# exlemon.net
KiCad netlist of a schematic drawn in EAGLE
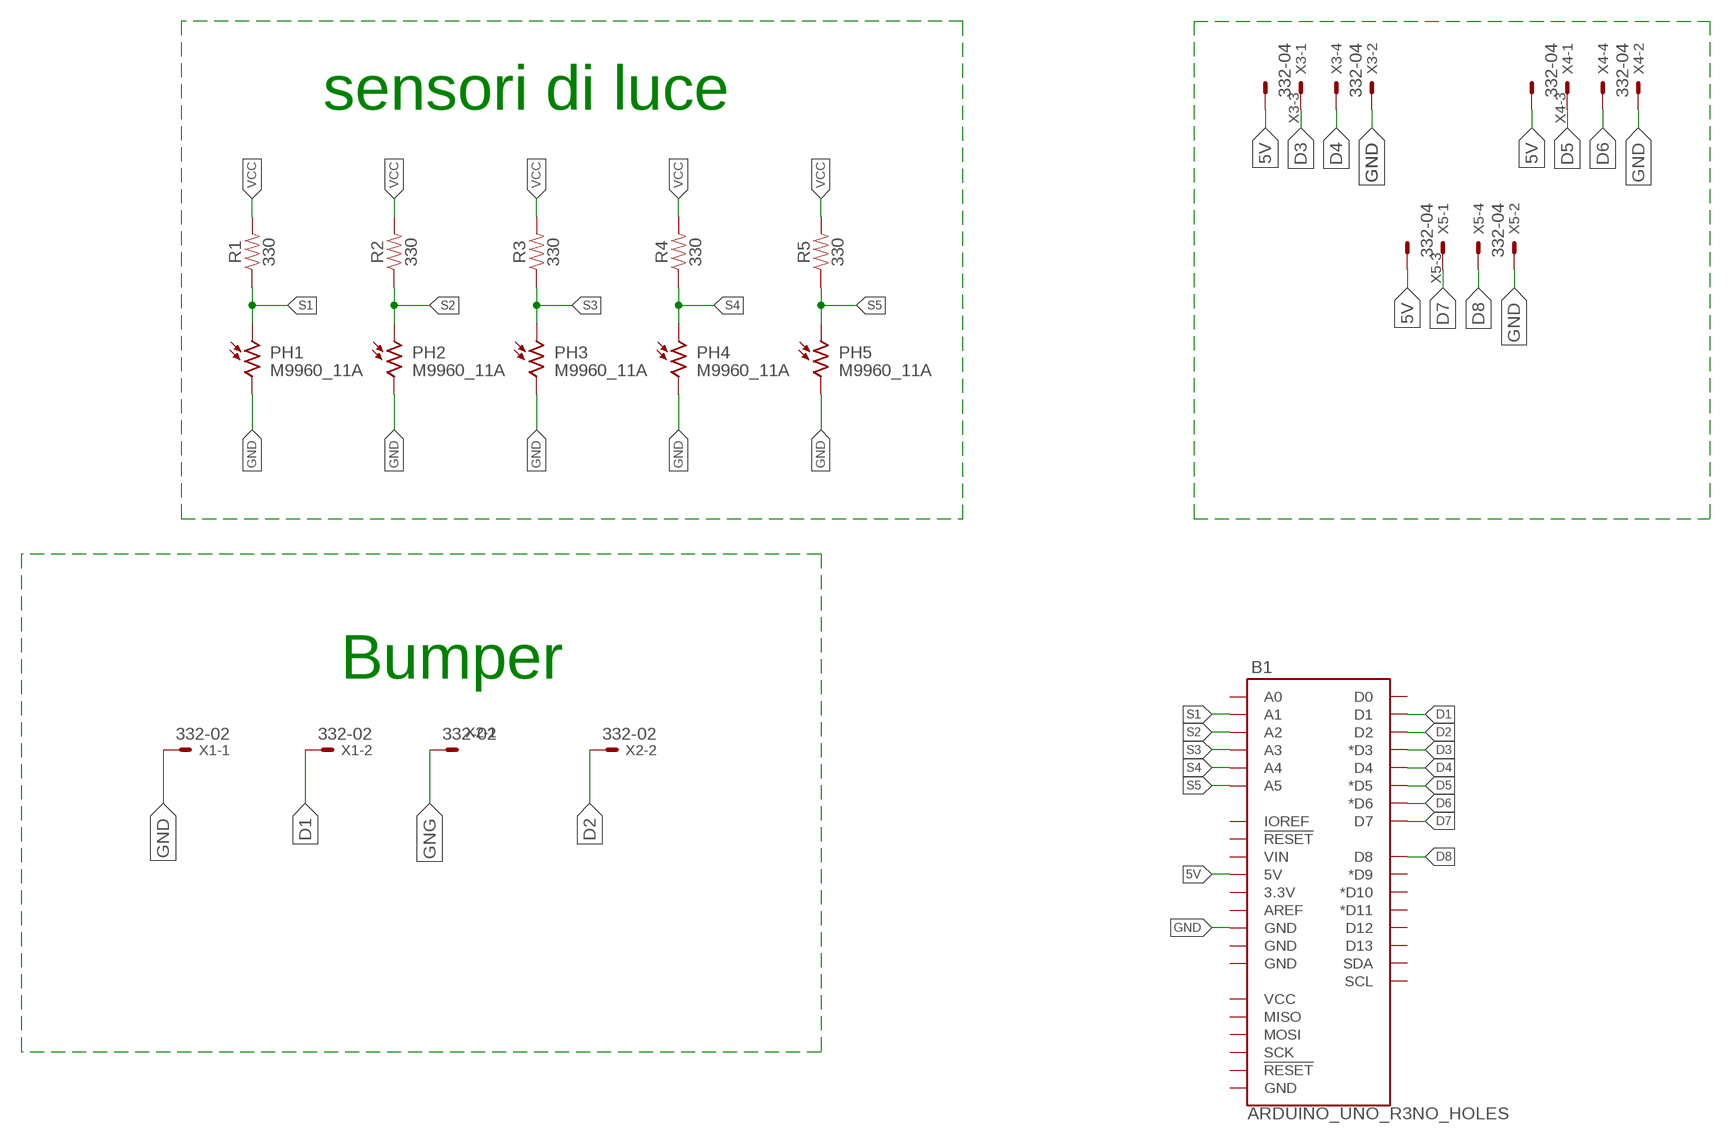
[diagram p0: schematic, sheet 1]

(export (version "E")
  (design (tool "Eeschema 10.0.6"))
  (components
    (comp (ref "B1")
      (value "ARDUINO_UNO_R3NO_HOLES")
      (footprint "eagle-import:ARDUINO_R3_NO_HOLES")
      (libsource (lib "eagle-import") (part "ARDUINO_UNO_R3NO_HOLES"))
    )
    (comp (ref "PH1")
      (value "M9960_11A")
      (footprint "eagle-import:M9960")
      (libsource (lib "eagle-import") (part "M9960_11A"))
    )
    (comp (ref "PH2")
      (value "M9960_11A")
      (footprint "eagle-import:M9960")
      (libsource (lib "eagle-import") (part "M9960_11A"))
    )
    (comp (ref "PH3")
      (value "M9960_11A")
      (footprint "eagle-import:M9960")
      (libsource (lib "eagle-import") (part "M9960_11A"))
    )
    (comp (ref "PH4")
      (value "M9960_11A")
      (footprint "eagle-import:M9960")
      (libsource (lib "eagle-import") (part "M9960_11A"))
    )
    (comp (ref "PH5")
      (value "M9960_11A")
      (footprint "eagle-import:M9960")
      (libsource (lib "eagle-import") (part "M9960_11A"))
    )
    (comp (ref "R1")
      (value "330")
      (footprint "eagle-import:AXIAL-0.3")
      (libsource (lib "eagle-import") (part "330OHM-HORIZ-1/10W-5%"))
    )
    (comp (ref "R2")
      (value "330")
      (footprint "eagle-import:AXIAL-0.3")
      (libsource (lib "eagle-import") (part "330OHM-HORIZ-1/10W-5%"))
    )
    (comp (ref "R3")
      (value "330")
      (footprint "eagle-import:AXIAL-0.3")
      (libsource (lib "eagle-import") (part "330OHM-HORIZ-1/10W-5%"))
    )
    (comp (ref "R4")
      (value "330")
      (footprint "eagle-import:AXIAL-0.3")
      (libsource (lib "eagle-import") (part "330OHM-HORIZ-1/10W-5%"))
    )
    (comp (ref "R5")
      (value "330")
      (footprint "eagle-import:AXIAL-0.3")
      (libsource (lib "eagle-import") (part "330OHM-HORIZ-1/10W-5%"))
    )
    (comp (ref "X1")
      (value "332-02")
      (footprint "eagle-import:332-02")
      (libsource (lib "eagle-import") (part "332-02"))
    )
    (comp (ref "X2")
      (value "332-02")
      (footprint "eagle-import:332-02")
      (libsource (lib "eagle-import") (part "332-02"))
    )
    (comp (ref "X3")
      (value "332-04")
      (footprint "eagle-import:332-04")
      (libsource (lib "eagle-import") (part "332-04"))
    )
    (comp (ref "X4")
      (value "332-04")
      (footprint "eagle-import:332-04")
      (libsource (lib "eagle-import") (part "332-04"))
    )
    (comp (ref "X5")
      (value "332-04")
      (footprint "eagle-import:332-04")
      (libsource (lib "eagle-import") (part "332-04"))
    )
  )
  (nets
    (net (code "2") (name "5V") (class "Default")
      (node (ref "B1") (pin "5V") (pinfunction "5V_5V") (pintype "bidirectional"))
      (node (ref "X3") (pin "3") (pinfunction "S_3") (pintype "passive"))
      (node (ref "X4") (pin "3") (pinfunction "S_3") (pintype "passive"))
      (node (ref "X5") (pin "3") (pinfunction "S_3") (pintype "passive"))
    )
    (net (code "3") (name "D1") (class "Default")
      (node (ref "B1") (pin "D1") (pinfunction "D1_D1") (pintype "bidirectional"))
      (node (ref "X1") (pin "2") (pinfunction "S_2") (pintype "passive"))
    )
    (net (code "4") (name "D2") (class "Default")
      (node (ref "B1") (pin "D2") (pinfunction "D2_D2") (pintype "bidirectional"))
      (node (ref "X2") (pin "2") (pinfunction "S_2") (pintype "passive"))
    )
    (net (code "5") (name "D3") (class "Default")
      (node (ref "B1") (pin "D3") (pinfunction "*D3_D3") (pintype "bidirectional"))
      (node (ref "X3") (pin "1") (pinfunction "S_1") (pintype "passive"))
    )
    (net (code "6") (name "D4") (class "Default")
      (node (ref "B1") (pin "D4") (pinfunction "D4_D4") (pintype "bidirectional"))
      (node (ref "X3") (pin "4") (pinfunction "S_4") (pintype "passive"))
    )
    (net (code "7") (name "D5") (class "Default")
      (node (ref "B1") (pin "D5") (pinfunction "*D5_D5") (pintype "bidirectional"))
      (node (ref "X4") (pin "1") (pinfunction "S_1") (pintype "passive"))
    )
    (net (code "8") (name "D6") (class "Default")
      (node (ref "B1") (pin "D6") (pinfunction "*D6_D6") (pintype "bidirectional"))
      (node (ref "X4") (pin "4") (pinfunction "S_4") (pintype "passive"))
    )
    (net (code "9") (name "D7") (class "Default")
      (node (ref "B1") (pin "D7") (pinfunction "D7_D7") (pintype "bidirectional"))
      (node (ref "X5") (pin "1") (pinfunction "S_1") (pintype "passive"))
    )
    (net (code "10") (name "D8") (class "Default")
      (node (ref "B1") (pin "D8") (pinfunction "D8_D8") (pintype "bidirectional"))
      (node (ref "X5") (pin "4") (pinfunction "S_4") (pintype "passive"))
    )
    (net (code "11") (name "GND") (class "Default")
      (node (ref "B1") (pin "GND@4") (pinfunction "GND_GND@4") (pintype "bidirectional"))
      (node (ref "PH1") (pin "2") (pinfunction "2_2") (pintype "passive"))
      (node (ref "PH2") (pin "2") (pinfunction "2_2") (pintype "passive"))
      (node (ref "PH3") (pin "2") (pinfunction "2_2") (pintype "passive"))
      (node (ref "PH4") (pin "2") (pinfunction "2_2") (pintype "passive"))
      (node (ref "PH5") (pin "2") (pinfunction "2_2") (pintype "passive"))
      (node (ref "X1") (pin "1") (pinfunction "S_1") (pintype "passive"))
      (node (ref "X3") (pin "2") (pinfunction "S_2") (pintype "passive"))
      (node (ref "X5") (pin "2") (pinfunction "S_2") (pintype "passive"))
    )
    (net (code "12") (name "GNG") (class "Default")
      (node (ref "X2") (pin "1") (pinfunction "S_1") (pintype "passive"))
    )
    (net (code "13") (name "S1") (class "Default")
      (node (ref "B1") (pin "A1") (pinfunction "A1_A1") (pintype "bidirectional"))
      (node (ref "PH1") (pin "1") (pinfunction "1_1") (pintype "passive"))
      (node (ref "R1") (pin "P$1") (pinfunction "1_P$1") (pintype "passive"))
    )
    (net (code "14") (name "S2") (class "Default")
      (node (ref "B1") (pin "A2") (pinfunction "A2_A2") (pintype "bidirectional"))
      (node (ref "PH2") (pin "1") (pinfunction "1_1") (pintype "passive"))
      (node (ref "R2") (pin "P$1") (pinfunction "1_P$1") (pintype "passive"))
    )
    (net (code "15") (name "S3") (class "Default")
      (node (ref "B1") (pin "A3") (pinfunction "A3_A3") (pintype "bidirectional"))
      (node (ref "PH3") (pin "1") (pinfunction "1_1") (pintype "passive"))
      (node (ref "R3") (pin "P$1") (pinfunction "1_P$1") (pintype "passive"))
    )
    (net (code "16") (name "S4") (class "Default")
      (node (ref "B1") (pin "A4") (pinfunction "A4_A4") (pintype "bidirectional"))
      (node (ref "PH4") (pin "1") (pinfunction "1_1") (pintype "passive"))
      (node (ref "R4") (pin "P$1") (pinfunction "1_P$1") (pintype "passive"))
    )
    (net (code "17") (name "S5") (class "Default")
      (node (ref "B1") (pin "A5") (pinfunction "A5_A5") (pintype "bidirectional"))
      (node (ref "PH5") (pin "1") (pinfunction "1_1") (pintype "passive"))
      (node (ref "R5") (pin "P$1") (pinfunction "1_P$1") (pintype "passive"))
    )
    (net (code "18") (name "VCC") (class "Default")
      (node (ref "R1") (pin "P$2") (pinfunction "2_P$2") (pintype "passive"))
      (node (ref "R2") (pin "P$2") (pinfunction "2_P$2") (pintype "passive"))
      (node (ref "R3") (pin "P$2") (pinfunction "2_P$2") (pintype "passive"))
      (node (ref "R4") (pin "P$2") (pinfunction "2_P$2") (pintype "passive"))
      (node (ref "R5") (pin "P$2") (pinfunction "2_P$2") (pintype "passive"))
    )
    (net (code "19") (name "unconnected-(B1-*D9-PadD9)") (class "Default")
      (node (ref "B1") (pin "D9") (pinfunction "*D9_D9") (pintype "bidirectional"))
    )
    (net (code "20") (name "unconnected-(B1-*D10-PadD10)") (class "Default")
      (node (ref "B1") (pin "D10") (pinfunction "*D10_D10") (pintype "bidirectional"))
    )
    (net (code "21") (name "unconnected-(B1-*D11-PadD11)") (class "Default")
      (node (ref "B1") (pin "D11") (pinfunction "*D11_D11") (pintype "bidirectional"))
    )
    (net (code "22") (name "unconnected-(B1-GND-PadGND@1)") (class "Default")
      (node (ref "B1") (pin "GND@1") (pinfunction "GND_GND@1") (pintype "bidirectional"))
    )
    (net (code "23") (name "unconnected-(B1-GND-PadGND@2)") (class "Default")
      (node (ref "B1") (pin "GND@2") (pinfunction "GND_GND@2") (pintype "bidirectional"))
    )
    (net (code "24") (name "unconnected-(B1-GND-PadGND@3)") (class "Default")
      (node (ref "B1") (pin "GND@3") (pinfunction "GND_GND@3") (pintype "bidirectional"))
    )
    (net (code "25") (name "unconnected-(B1-Pad3.3V)") (class "Default")
      (node (ref "B1") (pin "3.3V") (pinfunction "3.3V_3.3V") (pintype "bidirectional"))
    )
    (net (code "26") (name "unconnected-(B1-PadA0)") (class "Default")
      (node (ref "B1") (pin "A0") (pinfunction "A0_A0") (pintype "bidirectional"))
    )
    (net (code "27") (name "unconnected-(B1-PadAREF)") (class "Default")
      (node (ref "B1") (pin "AREF") (pinfunction "AREF_AREF") (pintype "bidirectional"))
    )
    (net (code "28") (name "unconnected-(B1-PadD0)") (class "Default")
      (node (ref "B1") (pin "D0") (pinfunction "D0_D0") (pintype "bidirectional"))
    )
    (net (code "29") (name "unconnected-(B1-PadD12)") (class "Default")
      (node (ref "B1") (pin "D12") (pinfunction "D12_D12") (pintype "bidirectional"))
    )
    (net (code "30") (name "unconnected-(B1-PadD13)") (class "Default")
      (node (ref "B1") (pin "D13") (pinfunction "D13_D13") (pintype "bidirectional"))
    )
    (net (code "31") (name "unconnected-(B1-PadIOREF)") (class "Default")
      (node (ref "B1") (pin "IOREF") (pinfunction "IOREF_IOREF") (pintype "bidirectional"))
    )
    (net (code "32") (name "unconnected-(B1-PadMISO)") (class "Default")
      (node (ref "B1") (pin "MISO") (pinfunction "MISO_MISO") (pintype "bidirectional"))
    )
    (net (code "33") (name "unconnected-(B1-PadMOSI)") (class "Default")
      (node (ref "B1") (pin "MOSI") (pinfunction "MOSI_MOSI") (pintype "bidirectional"))
    )
    (net (code "34") (name "unconnected-(B1-PadSCK)") (class "Default")
      (node (ref "B1") (pin "SCK") (pinfunction "SCK_SCK") (pintype "bidirectional"))
    )
    (net (code "35") (name "unconnected-(B1-PadSCL)") (class "Default")
      (node (ref "B1") (pin "SCL") (pinfunction "SCL_SCL") (pintype "bidirectional"))
    )
    (net (code "36") (name "unconnected-(B1-PadSDA)") (class "Default")
      (node (ref "B1") (pin "SDA") (pinfunction "SDA_SDA") (pintype "bidirectional"))
    )
    (net (code "37") (name "unconnected-(B1-PadVCC)") (class "Default")
      (node (ref "B1") (pin "VCC") (pinfunction "VCC_VCC") (pintype "bidirectional"))
    )
    (net (code "38") (name "unconnected-(B1-PadVIN)") (class "Default")
      (node (ref "B1") (pin "VIN") (pinfunction "VIN_VIN") (pintype "bidirectional"))
    )
    (net (code "39") (name "unconnected-(B1-~{RESET}-PadRESET@1)") (class "Default")
      (node (ref "B1") (pin "RESET@1") (pinfunction "~{RESET}_RESET@1") (pintype "bidirectional"))
    )
    (net (code "40") (name "unconnected-(B1-~{RESET}-PadRESET@2)") (class "Default")
      (node (ref "B1") (pin "RESET@2") (pinfunction "~{RESET}_RESET@2") (pintype "bidirectional"))
    )
    (net (code "41") (name "unconnected-(X4B-S-Pad2)") (class "Default")
      (node (ref "X4") (pin "2") (pinfunction "S_2") (pintype "passive"))
    )
  )
)
